# selflace.net
KiCad netlist of a schematic drawn in EAGLE
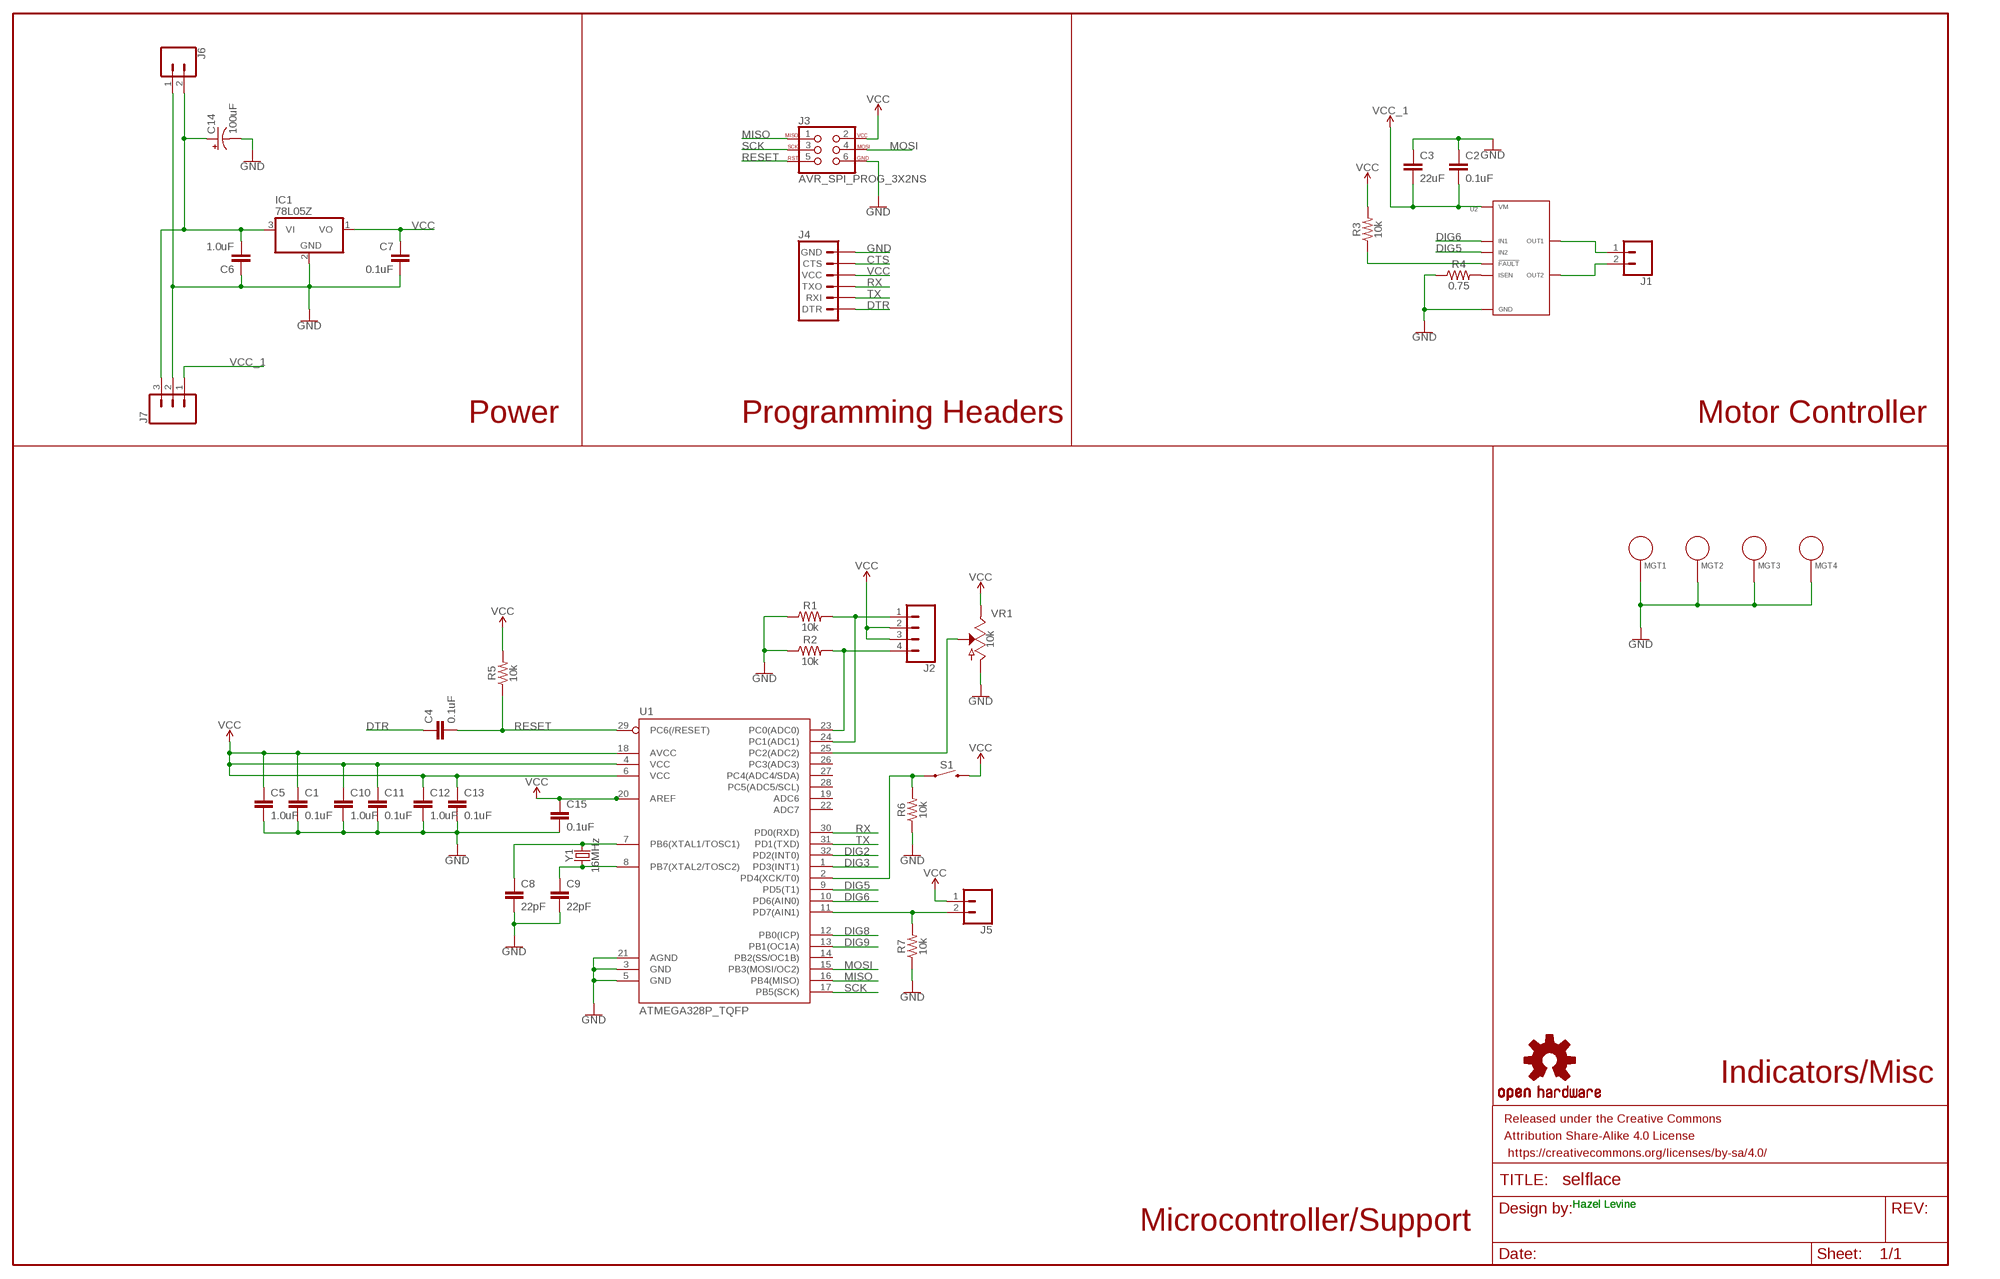
[diagram p0: schematic, sheet 1]

(export (version "E")
  (design (tool "Eeschema 10.0.6"))
  (components
    (comp (ref "C1")
      (value "0.1uF")
      (footprint "eagle-import:0603")
      (libsource (lib "eagle-import") (part "0.1UF-0603-25V-(+80/-20%)"))
    )
    (comp (ref "C2")
      (value "0.1uF")
      (footprint "eagle-import:0603")
      (libsource (lib "eagle-import") (part "0.1UF-0603-25V-(+80/-20%)"))
    )
    (comp (ref "C3")
      (value "22uF")
      (footprint "eagle-import:0805")
      (libsource (lib "eagle-import") (part "22UF-0805-6.3V-20%"))
    )
    (comp (ref "C4")
      (value "0.1uF")
      (footprint "eagle-import:0603")
      (libsource (lib "eagle-import") (part "0.1UF-0603-25V-(+80/-20%)"))
    )
    (comp (ref "C5")
      (value "1.0uF")
      (footprint "eagle-import:0603")
      (libsource (lib "eagle-import") (part "1.0UF-0603-16V-10%"))
    )
    (comp (ref "C6")
      (value "1.0uF")
      (footprint "eagle-import:0603")
      (libsource (lib "eagle-import") (part "1.0UF-0603-16V-10%"))
    )
    (comp (ref "C7")
      (value "0.1uF")
      (footprint "eagle-import:0603")
      (libsource (lib "eagle-import") (part "0.1UF-0603-25V-(+80/-20%)"))
    )
    (comp (ref "C8")
      (value "22pF")
      (footprint "eagle-import:0603")
      (libsource (lib "eagle-import") (part "22PF-0603-50V-5%"))
    )
    (comp (ref "C9")
      (value "22pF")
      (footprint "eagle-import:0603")
      (libsource (lib "eagle-import") (part "22PF-0603-50V-5%"))
    )
    (comp (ref "C10")
      (value "1.0uF")
      (footprint "eagle-import:0603")
      (libsource (lib "eagle-import") (part "1.0UF-0603-16V-10%"))
    )
    (comp (ref "C11")
      (value "0.1uF")
      (footprint "eagle-import:0603")
      (libsource (lib "eagle-import") (part "0.1UF-0603-25V-(+80/-20%)"))
    )
    (comp (ref "C12")
      (value "1.0uF")
      (footprint "eagle-import:0603")
      (libsource (lib "eagle-import") (part "1.0UF-0603-16V-10%"))
    )
    (comp (ref "C13")
      (value "0.1uF")
      (footprint "eagle-import:0603")
      (libsource (lib "eagle-import") (part "0.1UF-0603-25V-(+80/-20%)"))
    )
    (comp (ref "C14")
      (value "100uF")
      (footprint "eagle-import:NIC_10X10.5_CAP")
      (libsource (lib "eagle-import") (part "100UF-POLAR-10X10.5-63V-20%"))
    )
    (comp (ref "C15")
      (value "0.1uF")
      (footprint "eagle-import:0603")
      (libsource (lib "eagle-import") (part "0.1UF-0603-25V-(+80/-20%)"))
    )
    (comp (ref "FRAME1")
      (value "FRAME-LEDGER")
      (footprint "eagle-import:CREATIVE_COMMONS")
      (libsource (lib "eagle-import") (part "FRAME-LEDGER"))
    )
    (comp (ref "IC1")
      (value "78L05Z")
      (footprint "eagle-import:TO92")
      (libsource (lib "eagle-import") (part "78ZL05"))
    )
    (comp (ref "J1")
      (value "CONN_02")
      (footprint "eagle-import:1X02")
      (libsource (lib "eagle-import") (part "CONN_02"))
    )
    (comp (ref "J2")
      (value "CONN_04")
      (footprint "eagle-import:1X04")
      (libsource (lib "eagle-import") (part "CONN_04"))
    )
    (comp (ref "J3")
      (value "AVR_SPI_PROG_3X2NS")
      (footprint "eagle-import:2X3-NS")
      (libsource (lib "eagle-import") (part "AVR_SPI_PROG_3X2NS"))
    )
    (comp (ref "J4")
      (value "6_PIN_SERIAL_TARGETSILK")
      (footprint "eagle-import:6_PIN_SERIAL_TARGET_SIDE_W_SILK")
      (libsource (lib "eagle-import") (part "6_PIN_SERIAL_TARGETSILK"))
    )
    (comp (ref "J5")
      (value "CONN_02")
      (footprint "eagle-import:1X02")
      (libsource (lib "eagle-import") (part "CONN_02"))
    )
    (comp (ref "J6")
      (value "CONN_02JST-PTH-2")
      (footprint "eagle-import:JST-2-PTH")
      (libsource (lib "eagle-import") (part "CONN_02JST-PTH-2"))
    )
    (comp (ref "J7")
      (value "CONN_03")
      (footprint "eagle-import:1X03")
      (libsource (lib "eagle-import") (part "CONN_03"))
    )
    (comp (ref "LOGO1")
      (value "OSHW-LOGOM")
      (footprint "eagle-import:OSHW-LOGO-M")
      (libsource (lib "eagle-import") (part "OSHW-LOGOM"))
    )
    (comp (ref "MGT1")
      (value "BEAGLEBONEBLACK_MOUNTING_HOLE")
      (footprint "eagle-import:BEAGLEBONEBLACK_MOUNTING_HOLE")
      (libsource (lib "eagle-import") (part "BEAGLEBONEBLACK_MOUNTING_HOLE"))
    )
    (comp (ref "MGT2")
      (value "BEAGLEBONEBLACK_MOUNTING_HOLE")
      (footprint "eagle-import:BEAGLEBONEBLACK_MOUNTING_HOLE")
      (libsource (lib "eagle-import") (part "BEAGLEBONEBLACK_MOUNTING_HOLE"))
    )
    (comp (ref "MGT3")
      (value "BEAGLEBONEBLACK_MOUNTING_HOLE")
      (footprint "eagle-import:BEAGLEBONEBLACK_MOUNTING_HOLE")
      (libsource (lib "eagle-import") (part "BEAGLEBONEBLACK_MOUNTING_HOLE"))
    )
    (comp (ref "MGT4")
      (value "BEAGLEBONEBLACK_MOUNTING_HOLE")
      (footprint "eagle-import:BEAGLEBONEBLACK_MOUNTING_HOLE")
      (libsource (lib "eagle-import") (part "BEAGLEBONEBLACK_MOUNTING_HOLE"))
    )
    (comp (ref "R1")
      (value "10k")
      (footprint "eagle-import:0603")
      (libsource (lib "eagle-import") (part "10KOHM-0603-1/10W-1%"))
    )
    (comp (ref "R2")
      (value "10k")
      (footprint "eagle-import:0603")
      (libsource (lib "eagle-import") (part "10KOHM-0603-1/10W-1%"))
    )
    (comp (ref "R3")
      (value "10k")
      (footprint "eagle-import:0603")
      (libsource (lib "eagle-import") (part "10KOHM-0603-1/10W-1%"))
    )
    (comp (ref "R4")
      (value "0.75")
      (footprint "eagle-import:0805")
      (libsource (lib "eagle-import") (part "0.75OHM-0805-1/4W-1%"))
    )
    (comp (ref "R5")
      (value "10k")
      (footprint "eagle-import:0603")
      (libsource (lib "eagle-import") (part "10KOHM-0603-1/10W-1%"))
    )
    (comp (ref "R6")
      (value "10k")
      (footprint "eagle-import:0603")
      (libsource (lib "eagle-import") (part "10KOHM-0603-1/10W-1%"))
    )
    (comp (ref "R7")
      (value "10k")
      (footprint "eagle-import:0603")
      (libsource (lib "eagle-import") (part "10KOHM-0603-1/10W-1%"))
    )
    (comp (ref "S1")
      (value "MOMENTARY-SWITCH-SPST-PTH-6.0MM")
      (footprint "eagle-import:TACTILE_SWITCH_PTH_6.0MM")
      (libsource (lib "eagle-import") (part "MOMENTARY-SWITCH-SPST-PTH-6.0MM"))
    )
    (comp (ref "U1")
      (value "ATMEGA328P_TQFP")
      (footprint "eagle-import:TQFP32-08")
      (libsource (lib "eagle-import") (part "ATMEGA328P_TQFP"))
    )
    (comp (ref "U2")
      (value "DRV8872DDARQ1")
      (footprint "eagle-import:DRV8872_HSOP-8")
      (libsource (lib "eagle-import") (part "DRV8872DDARQ1"))
    )
    (comp (ref "VR1")
      (value "10k")
      (footprint "eagle-import:POT-PTH-ALPS")
      (libsource (lib "eagle-import") (part "POTENTIOMETER-PTH-9MM-1/20W-20%"))
    )
    (comp (ref "Y1")
      (value "16MHz")
      (footprint "eagle-import:HC49US")
      (libsource (lib "eagle-import") (part "CRYSTAL-16MHZPTH-HC49US"))
    )
  )
  (nets
    (net (code "1") (name "/CTS") (class "Default")
      (node (ref "J4") (pin "P$5") (pinfunction "CTS_P$5") (pintype "passive"))
    )
    (net (code "2") (name "/DIG2") (class "Default")
      (node (ref "U1") (pin "32") (pinfunction "PD2(INT0)_32") (pintype "bidirectional"))
    )
    (net (code "3") (name "/DIG3") (class "Default")
      (node (ref "U1") (pin "1") (pinfunction "PD3(INT1)_1") (pintype "bidirectional"))
    )
    (net (code "4") (name "/DIG5") (class "Default")
      (node (ref "U1") (pin "9") (pinfunction "PD5(T1)_9") (pintype "bidirectional"))
      (node (ref "U2") (pin "P$2") (pinfunction "IN2_P$2") (pintype "bidirectional"))
    )
    (net (code "5") (name "/DIG6") (class "Default")
      (node (ref "U1") (pin "10") (pinfunction "PD6(AIN0)_10") (pintype "bidirectional"))
      (node (ref "U2") (pin "P$3") (pinfunction "IN1_P$3") (pintype "bidirectional"))
    )
    (net (code "6") (name "/DIG8") (class "Default")
      (node (ref "U1") (pin "12") (pinfunction "PB0(ICP)_12") (pintype "bidirectional"))
    )
    (net (code "7") (name "/DIG9") (class "Default")
      (node (ref "U1") (pin "13") (pinfunction "PB1(OC1A)_13") (pintype "bidirectional"))
    )
    (net (code "8") (name "/DTR") (class "Default")
      (node (ref "C4") (pin "1") (pinfunction "1_1") (pintype "passive"))
      (node (ref "J4") (pin "P$1") (pinfunction "DTR_P$1") (pintype "passive"))
    )
    (net (code "9") (name "/MISO") (class "Default")
      (node (ref "J3") (pin "1") (pinfunction "1_1") (pintype "passive"))
      (node (ref "U1") (pin "16") (pinfunction "PB4(MISO)_16") (pintype "bidirectional"))
    )
    (net (code "10") (name "/MOSI") (class "Default")
      (node (ref "J3") (pin "4") (pinfunction "4_4") (pintype "passive"))
      (node (ref "U1") (pin "15") (pinfunction "PB3(MOSI/OC2)_15") (pintype "bidirectional"))
    )
    (net (code "11") (name "/RESET") (class "Default")
      (node (ref "C4") (pin "2") (pinfunction "2_2") (pintype "passive"))
      (node (ref "J3") (pin "5") (pinfunction "5_5") (pintype "passive"))
      (node (ref "R5") (pin "1") (pinfunction "1_1") (pintype "passive"))
      (node (ref "U1") (pin "29") (pinfunction "PC6(/RESET)_29") (pintype "bidirectional"))
    )
    (net (code "12") (name "/RX") (class "Default")
      (node (ref "J4") (pin "P$2") (pinfunction "TXO_P$2") (pintype "passive"))
      (node (ref "U1") (pin "30") (pinfunction "PD0(RXD)_30") (pintype "bidirectional"))
    )
    (net (code "13") (name "/SCK") (class "Default")
      (node (ref "J3") (pin "3") (pinfunction "3_3") (pintype "passive"))
      (node (ref "U1") (pin "17") (pinfunction "PB5(SCK)_17") (pintype "bidirectional"))
    )
    (net (code "14") (name "/TX") (class "Default")
      (node (ref "J4") (pin "P$3") (pinfunction "RXI_P$3") (pintype "passive"))
      (node (ref "U1") (pin "31") (pinfunction "PD1(TXD)_31") (pintype "bidirectional"))
    )
    (net (code "15") (name "GND") (class "Default")
      (node (ref "C1") (pin "2") (pinfunction "2_2") (pintype "passive"))
      (node (ref "C10") (pin "2") (pinfunction "2_2") (pintype "passive"))
      (node (ref "C11") (pin "2") (pinfunction "2_2") (pintype "passive"))
      (node (ref "C12") (pin "2") (pinfunction "2_2") (pintype "passive"))
      (node (ref "C13") (pin "2") (pinfunction "2_2") (pintype "passive"))
      (node (ref "C14") (pin "-") (pinfunction "-_-") (pintype "passive"))
      (node (ref "C15") (pin "2") (pinfunction "2_2") (pintype "passive"))
      (node (ref "C2") (pin "1") (pinfunction "1_1") (pintype "passive"))
      (node (ref "C3") (pin "1") (pinfunction "1_1") (pintype "passive"))
      (node (ref "C5") (pin "2") (pinfunction "2_2") (pintype "passive"))
      (node (ref "C6") (pin "1") (pinfunction "1_1") (pintype "passive"))
      (node (ref "C7") (pin "2") (pinfunction "2_2") (pintype "passive"))
      (node (ref "C8") (pin "2") (pinfunction "2_2") (pintype "passive"))
      (node (ref "C9") (pin "2") (pinfunction "2_2") (pintype "passive"))
      (node (ref "IC1") (pin "2") (pinfunction "GND_2") (pintype "passive"))
      (node (ref "J3") (pin "6") (pinfunction "6_6") (pintype "passive"))
      (node (ref "J4") (pin "P$6") (pinfunction "GND_P$6") (pintype "passive"))
      (node (ref "J6") (pin "1") (pinfunction "1_1") (pintype "passive"))
      (node (ref "J7") (pin "2") (pinfunction "2_2") (pintype "passive"))
      (node (ref "MGT1") (pin "P$1") (pinfunction "P$1_P$1") (pintype "bidirectional"))
      (node (ref "MGT2") (pin "P$1") (pinfunction "P$1_P$1") (pintype "bidirectional"))
      (node (ref "MGT3") (pin "P$1") (pinfunction "P$1_P$1") (pintype "bidirectional"))
      (node (ref "MGT4") (pin "P$1") (pinfunction "P$1_P$1") (pintype "bidirectional"))
      (node (ref "R1") (pin "1") (pinfunction "1_1") (pintype "passive"))
      (node (ref "R2") (pin "1") (pinfunction "1_1") (pintype "passive"))
      (node (ref "R4") (pin "1") (pinfunction "1_1") (pintype "passive"))
      (node (ref "R6") (pin "1") (pinfunction "1_1") (pintype "passive"))
      (node (ref "R7") (pin "1") (pinfunction "1_1") (pintype "passive"))
      (node (ref "U1") (pin "21") (pinfunction "AGND_21") (pintype "bidirectional"))
      (node (ref "U1") (pin "3") (pinfunction "GND_3") (pintype "bidirectional"))
      (node (ref "U1") (pin "5") (pinfunction "GND_5") (pintype "bidirectional"))
      (node (ref "U2") (pin "P$1") (pinfunction "GND_P$1") (pintype "bidirectional"))
      (node (ref "U2") (pin "P$10") (pinfunction "GND_P$10") (pintype "bidirectional"))
      (node (ref "U2") (pin "P$11") (pinfunction "GND_P$11") (pintype "bidirectional"))
      (node (ref "U2") (pin "P$12") (pinfunction "GND_P$12") (pintype "bidirectional"))
      (node (ref "U2") (pin "P$13") (pinfunction "GND_P$13") (pintype "bidirectional"))
      (node (ref "U2") (pin "P$14") (pinfunction "GND_P$14") (pintype "bidirectional"))
      (node (ref "U2") (pin "P$15") (pinfunction "GND_P$15") (pintype "bidirectional"))
      (node (ref "U2") (pin "P$9") (pinfunction "GND_P$9") (pintype "bidirectional"))
      (node (ref "VR1") (pin "P$3") (pinfunction "A_P$3") (pintype "passive"))
    )
    (net (code "16") (name "Net-(IC1-VI)") (class "Default")
      (node (ref "C14") (pin "+") (pinfunction "+_+") (pintype "passive"))
      (node (ref "C6") (pin "2") (pinfunction "2_2") (pintype "passive"))
      (node (ref "IC1") (pin "3") (pinfunction "VI_3") (pintype "input"))
      (node (ref "J6") (pin "2") (pinfunction "2_2") (pintype "passive"))
      (node (ref "J7") (pin "3") (pinfunction "3_3") (pintype "passive"))
    )
    (net (code "17") (name "Net-(U1-PB6(XTAL1{slash}TOSC1))") (class "Default")
      (node (ref "C8") (pin "1") (pinfunction "1_1") (pintype "passive"))
      (node (ref "U1") (pin "7") (pinfunction "PB6(XTAL1/TOSC1)_7") (pintype "bidirectional"))
      (node (ref "Y1") (pin "2") (pinfunction "2_2") (pintype "passive"))
    )
    (net (code "18") (name "Net-(U1-PB7(XTAL2{slash}TOSC2))") (class "Default")
      (node (ref "C9") (pin "1") (pinfunction "1_1") (pintype "passive"))
      (node (ref "U1") (pin "8") (pinfunction "PB7(XTAL2/TOSC2)_8") (pintype "bidirectional"))
      (node (ref "Y1") (pin "1") (pinfunction "1_1") (pintype "passive"))
    )
    (net (code "19") (name "Net-(U1-PC0(ADC0))") (class "Default")
      (node (ref "J2") (pin "4") (pinfunction "4_4") (pintype "passive"))
      (node (ref "R2") (pin "2") (pinfunction "2_2") (pintype "passive"))
      (node (ref "U1") (pin "23") (pinfunction "PC0(ADC0)_23") (pintype "bidirectional"))
    )
    (net (code "20") (name "Net-(U1-PC1(ADC1))") (class "Default")
      (node (ref "J2") (pin "1") (pinfunction "1_1") (pintype "passive"))
      (node (ref "R1") (pin "2") (pinfunction "2_2") (pintype "passive"))
      (node (ref "U1") (pin "24") (pinfunction "PC1(ADC1)_24") (pintype "bidirectional"))
    )
    (net (code "21") (name "Net-(U1-PC2(ADC2))") (class "Default")
      (node (ref "U1") (pin "25") (pinfunction "PC2(ADC2)_25") (pintype "bidirectional"))
      (node (ref "VR1") (pin "P$2") (pinfunction "S_P$2") (pintype "passive"))
    )
    (net (code "22") (name "Net-(U1-PD4(XCK{slash}T0))") (class "Default")
      (node (ref "R6") (pin "2") (pinfunction "2_2") (pintype "passive"))
      (node (ref "S1") (pin "1") (pinfunction "1_1") (pintype "passive"))
      (node (ref "U1") (pin "2") (pinfunction "PD4(XCK/T0)_2") (pintype "bidirectional"))
    )
    (net (code "23") (name "Net-(U1-PD7(AIN1))") (class "Default")
      (node (ref "J5") (pin "2") (pinfunction "2_2") (pintype "passive"))
      (node (ref "R7") (pin "2") (pinfunction "2_2") (pintype "passive"))
      (node (ref "U1") (pin "11") (pinfunction "PD7(AIN1)_11") (pintype "bidirectional"))
    )
    (net (code "24") (name "Net-(U2-ISEN)") (class "Default")
      (node (ref "R4") (pin "2") (pinfunction "2_2") (pintype "passive"))
      (node (ref "U2") (pin "P$7") (pinfunction "ISEN_P$7") (pintype "bidirectional"))
    )
    (net (code "25") (name "Net-(U2-OUT1)") (class "Default")
      (node (ref "J1") (pin "1") (pinfunction "1_1") (pintype "passive"))
      (node (ref "U2") (pin "P$6") (pinfunction "OUT1_P$6") (pintype "bidirectional"))
    )
    (net (code "26") (name "Net-(U2-OUT2)") (class "Default")
      (node (ref "J1") (pin "2") (pinfunction "2_2") (pintype "passive"))
      (node (ref "U2") (pin "P$8") (pinfunction "OUT2_P$8") (pintype "bidirectional"))
    )
    (net (code "27") (name "Net-(U2-~{FAULT})") (class "Default")
      (node (ref "R3") (pin "1") (pinfunction "1_1") (pintype "passive"))
      (node (ref "U2") (pin "P$4") (pinfunction "~{FAULT}_P$4") (pintype "bidirectional"))
    )
    (net (code "28") (name "VCC") (class "Default")
      (node (ref "C1") (pin "1") (pinfunction "1_1") (pintype "passive"))
      (node (ref "C10") (pin "1") (pinfunction "1_1") (pintype "passive"))
      (node (ref "C11") (pin "1") (pinfunction "1_1") (pintype "passive"))
      (node (ref "C12") (pin "1") (pinfunction "1_1") (pintype "passive"))
      (node (ref "C13") (pin "1") (pinfunction "1_1") (pintype "passive"))
      (node (ref "C15") (pin "1") (pinfunction "1_1") (pintype "passive"))
      (node (ref "C5") (pin "1") (pinfunction "1_1") (pintype "passive"))
      (node (ref "C7") (pin "1") (pinfunction "1_1") (pintype "passive"))
      (node (ref "IC1") (pin "1") (pinfunction "VO_1") (pintype "passive"))
      (node (ref "J2") (pin "2") (pinfunction "2_2") (pintype "passive"))
      (node (ref "J2") (pin "3") (pinfunction "3_3") (pintype "passive"))
      (node (ref "J3") (pin "2") (pinfunction "2_2") (pintype "passive"))
      (node (ref "J4") (pin "P$4") (pinfunction "VCC_P$4") (pintype "passive"))
      (node (ref "J5") (pin "1") (pinfunction "1_1") (pintype "passive"))
      (node (ref "R3") (pin "2") (pinfunction "2_2") (pintype "passive"))
      (node (ref "R5") (pin "2") (pinfunction "2_2") (pintype "passive"))
      (node (ref "S1") (pin "3") (pinfunction "2_3") (pintype "passive"))
      (node (ref "U1") (pin "18") (pinfunction "AVCC_18") (pintype "bidirectional"))
      (node (ref "U1") (pin "20") (pinfunction "AREF_20") (pintype "bidirectional"))
      (node (ref "U1") (pin "4") (pinfunction "VCC_4") (pintype "bidirectional"))
      (node (ref "U1") (pin "6") (pinfunction "VCC_6") (pintype "bidirectional"))
      (node (ref "VR1") (pin "P$1") (pinfunction "E_P$1") (pintype "passive"))
    )
    (net (code "29") (name "VCC_1") (class "Default")
      (node (ref "C2") (pin "2") (pinfunction "2_2") (pintype "passive"))
      (node (ref "C3") (pin "2") (pinfunction "2_2") (pintype "passive"))
      (node (ref "J7") (pin "1") (pinfunction "1_1") (pintype "passive"))
      (node (ref "U2") (pin "P$5") (pinfunction "VM_P$5") (pintype "bidirectional"))
    )
    (net (code "30") (name "unconnected-(U1-ADC6-Pad19)") (class "Default")
      (node (ref "U1") (pin "19") (pinfunction "ADC6_19") (pintype "bidirectional"))
    )
    (net (code "31") (name "unconnected-(U1-ADC7-Pad22)") (class "Default")
      (node (ref "U1") (pin "22") (pinfunction "ADC7_22") (pintype "bidirectional"))
    )
    (net (code "32") (name "unconnected-(U1-PB2(SS{slash}OC1B)-Pad14)") (class "Default")
      (node (ref "U1") (pin "14") (pinfunction "PB2(SS/OC1B)_14") (pintype "bidirectional"))
    )
    (net (code "33") (name "unconnected-(U1-PC3(ADC3)-Pad26)") (class "Default")
      (node (ref "U1") (pin "26") (pinfunction "PC3(ADC3)_26") (pintype "bidirectional"))
    )
    (net (code "34") (name "unconnected-(U1-PC4(ADC4{slash}SDA)-Pad27)") (class "Default")
      (node (ref "U1") (pin "27") (pinfunction "PC4(ADC4/SDA)_27") (pintype "bidirectional"))
    )
    (net (code "35") (name "unconnected-(U1-PC5(ADC5{slash}SCL)-Pad28)") (class "Default")
      (node (ref "U1") (pin "28") (pinfunction "PC5(ADC5/SCL)_28") (pintype "bidirectional"))
    )
  )
)
